# board.net
KiCad netlist of a schematic drawn in EAGLE
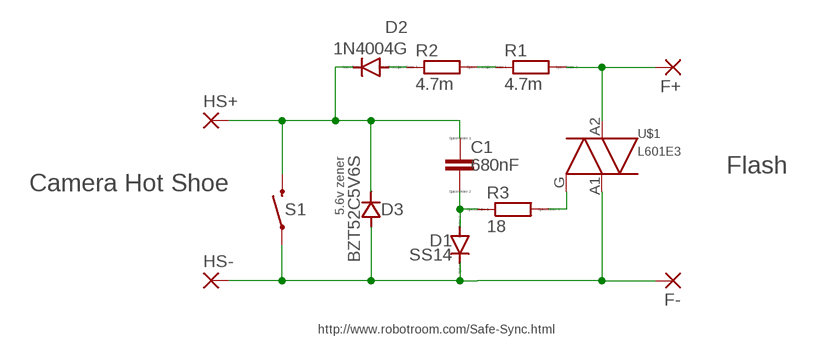
[diagram p0: schematic, sheet 1]

(export (version "E")
  (design (tool "Eeschema 10.0.6"))
  (components
    (comp (ref "C1")
      (value "680nF")
      (footprint "eagle-import:C0603")
      (libsource (lib "eagle-import") (part "CC0603"))
    )
    (comp (ref "D1")
      (value "SS14")
      (footprint "eagle-import:DO214AC")
      (libsource (lib "eagle-import") (part "DIODE-DO214AC"))
    )
    (comp (ref "D2")
      (value "1N4004G")
      (footprint "eagle-import:DO214AC")
      (libsource (lib "eagle-import") (part "DIODE-DO214AC"))
    )
    (comp (ref "D3")
      (value "BZT52C5V6S")
      (footprint "eagle-import:SOD323")
      (fields (field (name "MPN") "CDSOD323-T05C"))
      (libsource (lib "eagle-import") (part "DSOD323"))
    )
    (comp (ref "F+")
      (value "1,6/0,8")
      (footprint "eagle-import:1,6_0,8")
      (libsource (lib "eagle-import") (part "1,6/0,8"))
    )
    (comp (ref "F-")
      (value "1,6/0,8")
      (footprint "eagle-import:1,6_0,8")
      (libsource (lib "eagle-import") (part "1,6/0,8"))
    )
    (comp (ref "HS+")
      (value "1,6/0,8")
      (footprint "eagle-import:1,6_0,8")
      (libsource (lib "eagle-import") (part "1,6/0,8"))
    )
    (comp (ref "HS-")
      (value "1,6/0,8")
      (footprint "eagle-import:1,6_0,8")
      (libsource (lib "eagle-import") (part "1,6/0,8"))
    )
    (comp (ref "R1")
      (value "4.7m")
      (footprint "eagle-import:R0603")
      (libsource (lib "eagle-import") (part "RR0603"))
    )
    (comp (ref "R2")
      (value "4.7m")
      (footprint "eagle-import:R0603")
      (libsource (lib "eagle-import") (part "RR0603"))
    )
    (comp (ref "R3")
      (value "18")
      (footprint "eagle-import:R0603")
      (libsource (lib "eagle-import") (part "RR0603"))
    )
    (comp (ref "S1")
      (value "MOMENTARY-SWITCH-SPST-SMD-6.0X3.5MM")
      (footprint "eagle-import:TACTILE_SWITCH_SMD_6.0X3.5MM")
      (libsource (lib "eagle-import") (part "MOMENTARY-SWITCH-SPST-SMD-6.0X3.5MM"))
    )
    (comp (ref "U$1")
      (value "L601E3")
      (footprint "eagle-import:TO92E")
      (libsource (lib "eagle-import") (part "L601E3"))
    )
  )
  (nets
    (net (code "1") (name "Net-(C1-Pad2)") (class "Default")
      (node (ref "C1") (pin "2") (pinfunction "2_2") (pintype "passive"))
      (node (ref "D1") (pin "A") (pinfunction "A_A") (pintype "passive"))
      (node (ref "R3") (pin "1") (pinfunction "1_1") (pintype "passive"))
    )
    (net (code "2") (name "Net-(D2-PadA)") (class "Default")
      (node (ref "D2") (pin "A") (pinfunction "A_A") (pintype "passive"))
      (node (ref "R2") (pin "1") (pinfunction "1_1") (pintype "passive"))
    )
    (net (code "3") (name "Net-(D3-A)") (class "Default")
      (node (ref "D1") (pin "C") (pinfunction "C_C") (pintype "passive"))
      (node (ref "D3") (pin "2") (pinfunction "A_2") (pintype "passive"))
      (node (ref "F-") (pin "1") (pinfunction "P_1") (pintype "passive"))
      (node (ref "HS-") (pin "1") (pinfunction "P_1") (pintype "passive"))
      (node (ref "S1") (pin "1") (pinfunction "1_1") (pintype "passive"))
      (node (ref "U$1") (pin "A1") (pinfunction "A1_A1") (pintype "bidirectional"))
    )
    (net (code "4") (name "Net-(D3-C)") (class "Default")
      (node (ref "C1") (pin "1") (pinfunction "1_1") (pintype "passive"))
      (node (ref "D2") (pin "C") (pinfunction "C_C") (pintype "passive"))
      (node (ref "D3") (pin "1") (pinfunction "C_1") (pintype "passive"))
      (node (ref "HS+") (pin "1") (pinfunction "P_1") (pintype "passive"))
      (node (ref "S1") (pin "2") (pinfunction "2_2") (pintype "passive"))
    )
    (net (code "5") (name "Net-(F+-P)") (class "Default")
      (node (ref "F+") (pin "1") (pinfunction "P_1") (pintype "passive"))
      (node (ref "R1") (pin "2") (pinfunction "2_2") (pintype "passive"))
      (node (ref "U$1") (pin "A2") (pinfunction "A2_A2") (pintype "bidirectional"))
    )
    (net (code "6") (name "Net-(R1-Pad1)") (class "Default")
      (node (ref "R1") (pin "1") (pinfunction "1_1") (pintype "passive"))
      (node (ref "R2") (pin "2") (pinfunction "2_2") (pintype "passive"))
    )
    (net (code "7") (name "Net-(R3-Pad2)") (class "Default")
      (node (ref "R3") (pin "2") (pinfunction "2_2") (pintype "passive"))
      (node (ref "U$1") (pin "G") (pinfunction "G_G") (pintype "bidirectional"))
    )
  )
)
